# 5_-CONNECTORS.net
KiCad netlist of a schematic drawn in Altium Designer
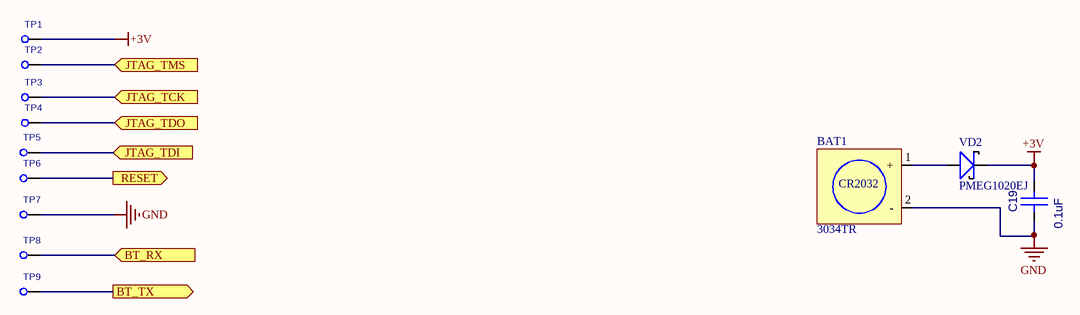
[diagram p0: [5]-CONNECTORS.SchDoc]

(export (version "E")
  (design (tool "Eeschema 10.0.6"))
  (components
    (comp (ref "BAT1")
      (value "3034TR")
      (footprint "3034-TR")
      (description "CR2032 holder smd")
      (libsource (lib "fizik_lib") (part "3034"))
    )
    (comp (ref "C19")
      (value "0.1uF")
      (footprint "CC0603")
      (description "CC0603")
      (libsource (lib "fizik_lib") (part "CC0603"))
    )
    (comp (ref "TP1")
      (value "TESTPOINT1")
      (footprint "TESTPOINT1")
      (libsource (lib "fizik_lib") (part "TESTPOINT1"))
    )
    (comp (ref "TP2")
      (value "TESTPOINT1")
      (footprint "TESTPOINT1")
      (libsource (lib "fizik_lib") (part "TESTPOINT1"))
    )
    (comp (ref "TP3")
      (value "TESTPOINT1")
      (footprint "TESTPOINT1")
      (libsource (lib "fizik_lib") (part "TESTPOINT1"))
    )
    (comp (ref "TP4")
      (value "TESTPOINT1")
      (footprint "TESTPOINT1")
      (libsource (lib "fizik_lib") (part "TESTPOINT1"))
    )
    (comp (ref "TP5")
      (value "TESTPOINT1")
      (footprint "TESTPOINT1")
      (libsource (lib "fizik_lib") (part "TESTPOINT1"))
    )
    (comp (ref "TP6")
      (value "TESTPOINT1")
      (footprint "TESTPOINT1")
      (libsource (lib "fizik_lib") (part "TESTPOINT1"))
    )
    (comp (ref "TP7")
      (value "TESTPOINT1")
      (footprint "TESTPOINT1")
      (libsource (lib "fizik_lib") (part "TESTPOINT1"))
    )
    (comp (ref "TP8")
      (value "TESTPOINT1")
      (footprint "TESTPOINT1")
      (libsource (lib "fizik_lib") (part "TESTPOINT1"))
    )
    (comp (ref "TP9")
      (value "TESTPOINT1")
      (footprint "TESTPOINT1")
      (libsource (lib "fizik_lib") (part "TESTPOINT1"))
    )
    (comp (ref "VD2")
      (value "PMEG1020EJ")
      (footprint "SOD323")
      (libsource (lib "fizik_lib") (part "PMEG2010"))
    )
  )
  (nets
    (net (code "1") (name "+3V") (class "Default")
      (node (ref "C19") (pin "2") (pinfunction "B_2") (pintype "passive"))
      (node (ref "TP1") (pin "1") (pintype "passive"))
      (node (ref "VD2") (pin "2") (pinfunction "K_2") (pintype "passive"))
    )
    (net (code "2") (name "/BT_RX") (class "Default") (node (ref "TP8") (pin "1") (pintype "passive")))
    (net (code "3") (name "/BT_TX") (class "Default") (node (ref "TP9") (pin "1") (pintype "passive")))
    (net (code "4") (name "/JTAG_TCK") (class "Default") (node (ref "TP3") (pin "1") (pintype "passive")))
    (net (code "5") (name "/JTAG_TDI") (class "Default") (node (ref "TP5") (pin "1") (pintype "passive")))
    (net (code "6") (name "/JTAG_TDO") (class "Default") (node (ref "TP4") (pin "1") (pintype "passive")))
    (net (code "7") (name "/JTAG_TMS") (class "Default") (node (ref "TP2") (pin "1") (pintype "passive")))
    (net (code "8") (name "/RESET") (class "Default") (node (ref "TP6") (pin "1") (pintype "passive")))
    (net (code "9") (name "GND") (class "Default")
      (node (ref "BAT1") (pin "2") (pinfunction "-_2") (pintype "passive"))
      (node (ref "C19") (pin "1") (pinfunction "A_1") (pintype "passive"))
      (node (ref "TP7") (pin "1") (pintype "passive"))
    )
    (net (code "10") (name "Net-(BAT1-+)") (class "Default")
      (node (ref "BAT1") (pin "1") (pinfunction "+_1") (pintype "passive"))
      (node (ref "VD2") (pin "1") (pinfunction "A_1") (pintype "passive"))
    )
  )
)
